# ADC_AD9208.net
KiCad netlist of a schematic drawn in Altium Designer
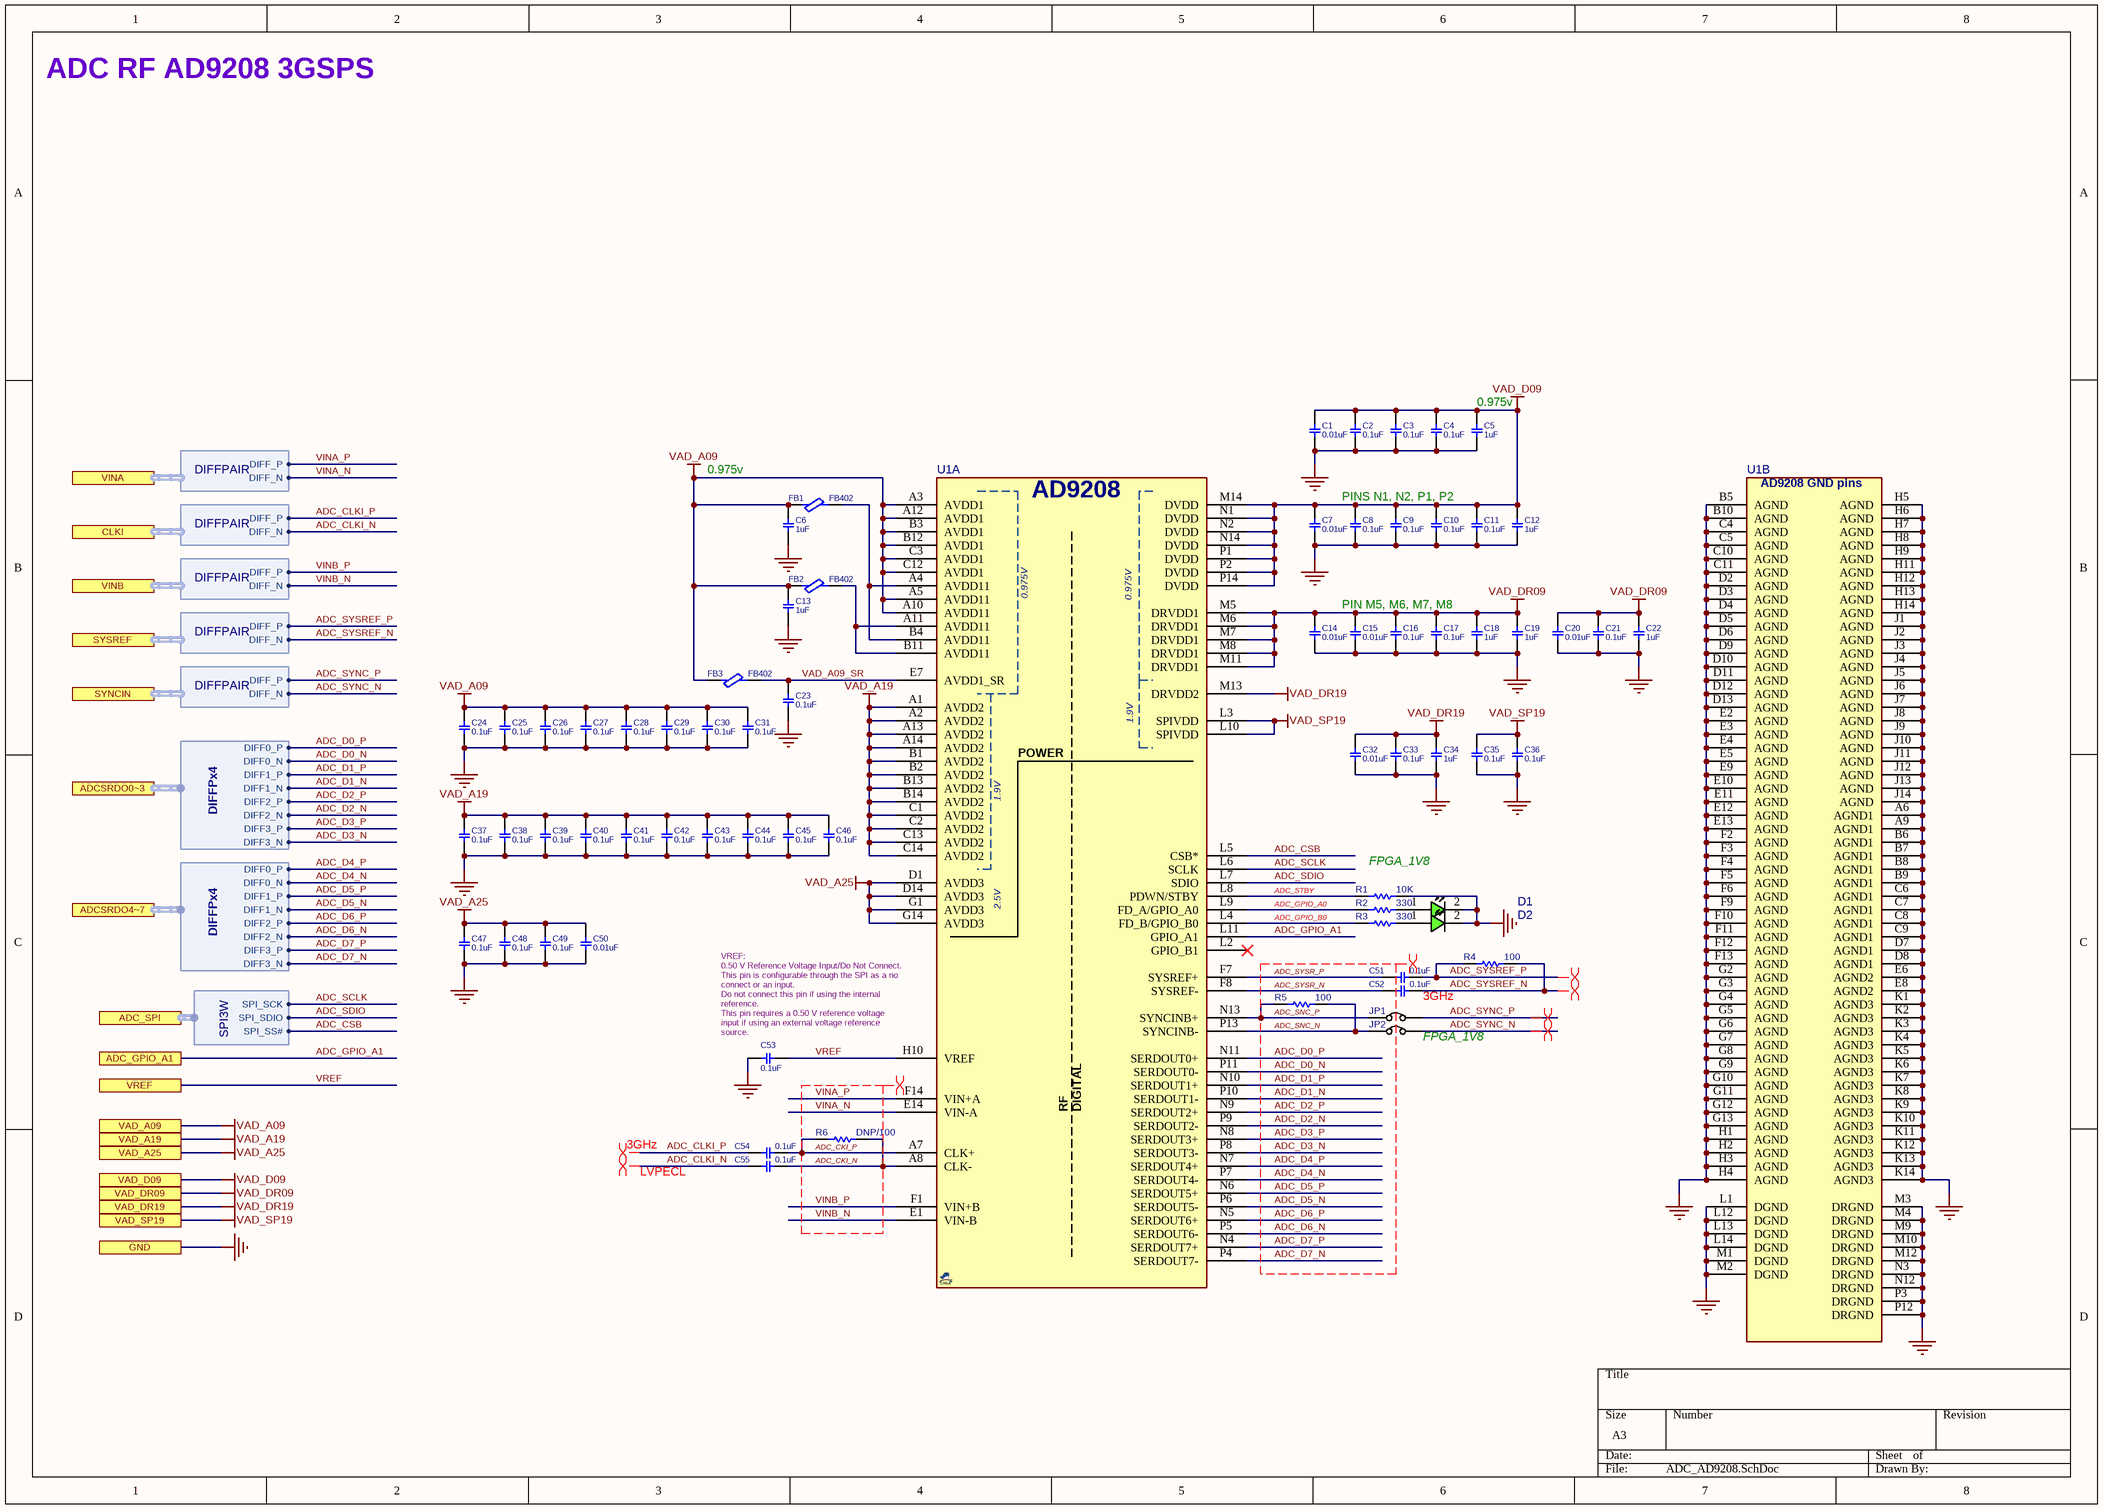
[diagram p0: ADC_AD9208.SchDoc]

(export (version "E")
  (design (tool "Eeschema 10.0.6"))
  (components
    (comp (ref "C1")
      (value "0.01uF")
      (footprint "C0402")
      (description "CAP, MLCC")
      (fields (field (name "MANF_P#") "MANF_PART#") (field (name "MANF") "Murata"))
      (libsource (lib "passive_smd") (part "CAP_SMD_MLCC"))
    )
    (comp (ref "C2")
      (value "0.1uF")
      (footprint "C0402")
      (description "CAP, MLCC")
      (libsource (lib "mlcc_smd_passive") (part "CAP_SMD_MLCC_100n50T"))
    )
    (comp (ref "C3")
      (value "0.1uF")
      (footprint "C0402")
      (description "CAP, MLCC")
      (libsource (lib "mlcc_smd_passive") (part "CAP_SMD_MLCC_100n50T"))
    )
    (comp (ref "C4")
      (value "0.1uF")
      (footprint "C0402")
      (description "CAP, MLCC")
      (libsource (lib "mlcc_smd_passive") (part "CAP_SMD_MLCC_100n50T"))
    )
    (comp (ref "C5")
      (value "1uF")
      (footprint "C0402")
      (description "CAP, MLCC")
      (fields (field (name "MANF_P#") "MANF_PART#") (field (name "MANF") "Murata"))
      (libsource (lib "passive_smd") (part "CAP_SMD_MLCC"))
    )
    (comp (ref "C6")
      (value "1uF")
      (footprint "C0402")
      (description "CAP, MLCC")
      (libsource (lib "mlcc_smd_passive") (part "CAP_SMD_MLCC_100n50T"))
    )
    (comp (ref "C7")
      (value "0.01uF")
      (footprint "C0402")
      (description "CAP, MLCC")
      (fields (field (name "MANF_P#") "MANF_PART#") (field (name "MANF") "Murata"))
      (libsource (lib "passive_smd") (part "CAP_SMD_MLCC"))
    )
    (comp (ref "C8")
      (value "0.1uF")
      (footprint "C0402")
      (description "CAP, MLCC")
      (libsource (lib "mlcc_smd_passive") (part "CAP_SMD_MLCC_100n50T"))
    )
    (comp (ref "C9")
      (value "0.1uF")
      (footprint "C0402")
      (description "CAP, MLCC")
      (libsource (lib "mlcc_smd_passive") (part "CAP_SMD_MLCC_100n50T"))
    )
    (comp (ref "C10")
      (value "0.1uF")
      (footprint "C0402")
      (description "CAP, MLCC")
      (libsource (lib "mlcc_smd_passive") (part "CAP_SMD_MLCC_100n50T"))
    )
    (comp (ref "C11")
      (value "0.1uF")
      (footprint "C0402")
      (description "CAP, MLCC")
      (libsource (lib "mlcc_smd_passive") (part "CAP_SMD_MLCC_100n50T"))
    )
    (comp (ref "C12")
      (value "1uF")
      (footprint "C0402")
      (description "CAP, MLCC")
      (fields (field (name "MANF_P#") "MANF_PART#") (field (name "MANF") "Murata"))
      (libsource (lib "passive_smd") (part "CAP_SMD_MLCC"))
    )
    (comp (ref "C13")
      (value "1uF")
      (footprint "C0402")
      (description "CAP, MLCC")
      (libsource (lib "mlcc_smd_passive") (part "CAP_SMD_MLCC_100n50T"))
    )
    (comp (ref "C14")
      (value "0.01uF")
      (footprint "C0402")
      (description "CAP, MLCC")
      (fields (field (name "MANF_P#") "MANF_PART#") (field (name "MANF") "Murata"))
      (libsource (lib "passive_smd") (part "CAP_SMD_MLCC"))
    )
    (comp (ref "C15")
      (value "0.01uF")
      (footprint "C0402")
      (description "CAP, MLCC")
      (fields (field (name "MANF_P#") "MANF_PART#") (field (name "MANF") "Murata"))
      (libsource (lib "passive_smd") (part "CAP_SMD_MLCC"))
    )
    (comp (ref "C16")
      (value "0.1uF")
      (footprint "C0402")
      (description "CAP, MLCC")
      (libsource (lib "mlcc_smd_passive") (part "CAP_SMD_MLCC_100n50T"))
    )
    (comp (ref "C17")
      (value "0.1uF")
      (footprint "C0402")
      (description "CAP, MLCC")
      (libsource (lib "mlcc_smd_passive") (part "CAP_SMD_MLCC_100n50T"))
    )
    (comp (ref "C18")
      (value "1uF")
      (footprint "C0402")
      (description "CAP, MLCC")
      (fields (field (name "MANF_P#") "MANF_PART#") (field (name "MANF") "Murata"))
      (libsource (lib "passive_smd") (part "CAP_SMD_MLCC"))
    )
    (comp (ref "C19")
      (value "1uF")
      (footprint "C0402")
      (description "CAP, MLCC")
      (fields (field (name "MANF_P#") "MANF_PART#") (field (name "MANF") "Murata"))
      (libsource (lib "passive_smd") (part "CAP_SMD_MLCC"))
    )
    (comp (ref "C20")
      (value "0.01uF")
      (footprint "C0402")
      (description "CAP, MLCC")
      (fields (field (name "MANF_P#") "MANF_PART#") (field (name "MANF") "Murata"))
      (libsource (lib "passive_smd") (part "CAP_SMD_MLCC"))
    )
    (comp (ref "C21")
      (value "0.1uF")
      (footprint "C0402")
      (description "CAP, MLCC")
      (libsource (lib "mlcc_smd_passive") (part "CAP_SMD_MLCC_100n50T"))
    )
    (comp (ref "C22")
      (value "1uF")
      (footprint "C0402")
      (description "CAP, MLCC")
      (fields (field (name "MANF_P#") "MANF_PART#") (field (name "MANF") "Murata"))
      (libsource (lib "passive_smd") (part "CAP_SMD_MLCC"))
    )
    (comp (ref "C23")
      (value "0.1uF")
      (footprint "C0402")
      (description "CAP, MLCC")
      (libsource (lib "mlcc_smd_passive") (part "CAP_SMD_MLCC_100n50T"))
    )
    (comp (ref "C24")
      (value "0.1uF")
      (footprint "C0402")
      (description "CAP, MLCC")
      (libsource (lib "mlcc_smd_passive") (part "CAP_SMD_MLCC_100n50T"))
    )
    (comp (ref "C25")
      (value "0.1uF")
      (footprint "C0402")
      (description "CAP, MLCC")
      (libsource (lib "mlcc_smd_passive") (part "CAP_SMD_MLCC_100n50T"))
    )
    (comp (ref "C26")
      (value "0.1uF")
      (footprint "C0402")
      (description "CAP, MLCC")
      (libsource (lib "mlcc_smd_passive") (part "CAP_SMD_MLCC_100n50T"))
    )
    (comp (ref "C27")
      (value "0.1uF")
      (footprint "C0402")
      (description "CAP, MLCC")
      (libsource (lib "mlcc_smd_passive") (part "CAP_SMD_MLCC_100n50T"))
    )
    (comp (ref "C28")
      (value "0.1uF")
      (footprint "C0402")
      (description "CAP, MLCC")
      (libsource (lib "mlcc_smd_passive") (part "CAP_SMD_MLCC_100n50T"))
    )
    (comp (ref "C29")
      (value "0.1uF")
      (footprint "C0402")
      (description "CAP, MLCC")
      (libsource (lib "mlcc_smd_passive") (part "CAP_SMD_MLCC_100n50T"))
    )
    (comp (ref "C30")
      (value "0.1uF")
      (footprint "C0402")
      (description "CAP, MLCC")
      (libsource (lib "mlcc_smd_passive") (part "CAP_SMD_MLCC_100n50T"))
    )
    (comp (ref "C31")
      (value "0.1uF")
      (footprint "C0402")
      (description "CAP, MLCC")
      (libsource (lib "mlcc_smd_passive") (part "CAP_SMD_MLCC_100n50T"))
    )
    (comp (ref "C32")
      (value "0.01uF")
      (footprint "C0402")
      (description "CAP, MLCC")
      (fields (field (name "MANF_P#") "MANF_PART#") (field (name "MANF") "Murata"))
      (libsource (lib "passive_smd") (part "CAP_SMD_MLCC"))
    )
    (comp (ref "C33")
      (value "0.1uF")
      (footprint "C0402")
      (description "CAP, MLCC")
      (libsource (lib "mlcc_smd_passive") (part "CAP_SMD_MLCC_100n50T"))
    )
    (comp (ref "C34")
      (value "1uF")
      (footprint "C0402")
      (description "CAP, MLCC")
      (fields (field (name "MANF_P#") "MANF_PART#") (field (name "MANF") "Murata"))
      (libsource (lib "passive_smd") (part "CAP_SMD_MLCC"))
    )
    (comp (ref "C35")
      (value "0.1uF")
      (footprint "C0402")
      (description "CAP, MLCC")
      (libsource (lib "mlcc_smd_passive") (part "CAP_SMD_MLCC_100n50T"))
    )
    (comp (ref "C36")
      (value "0.1uF")
      (footprint "C0402")
      (description "CAP, MLCC")
      (libsource (lib "mlcc_smd_passive") (part "CAP_SMD_MLCC_100n50T"))
    )
    (comp (ref "C37")
      (value "0.1uF")
      (footprint "C0402")
      (description "CAP, MLCC")
      (libsource (lib "mlcc_smd_passive") (part "CAP_SMD_MLCC_100n50T"))
    )
    (comp (ref "C38")
      (value "0.1uF")
      (footprint "C0402")
      (description "CAP, MLCC")
      (libsource (lib "mlcc_smd_passive") (part "CAP_SMD_MLCC_100n50T"))
    )
    (comp (ref "C39")
      (value "0.1uF")
      (footprint "C0402")
      (description "CAP, MLCC")
      (libsource (lib "mlcc_smd_passive") (part "CAP_SMD_MLCC_100n50T"))
    )
    (comp (ref "C40")
      (value "0.1uF")
      (footprint "C0402")
      (description "CAP, MLCC")
      (libsource (lib "mlcc_smd_passive") (part "CAP_SMD_MLCC_100n50T"))
    )
    (comp (ref "C41")
      (value "0.1uF")
      (footprint "C0402")
      (description "CAP, MLCC")
      (libsource (lib "mlcc_smd_passive") (part "CAP_SMD_MLCC_100n50T"))
    )
    (comp (ref "C42")
      (value "0.1uF")
      (footprint "C0402")
      (description "CAP, MLCC")
      (libsource (lib "mlcc_smd_passive") (part "CAP_SMD_MLCC_100n50T"))
    )
    (comp (ref "C43")
      (value "0.1uF")
      (footprint "C0402")
      (description "CAP, MLCC")
      (libsource (lib "mlcc_smd_passive") (part "CAP_SMD_MLCC_100n50T"))
    )
    (comp (ref "C44")
      (value "0.1uF")
      (footprint "C0402")
      (description "CAP, MLCC")
      (libsource (lib "mlcc_smd_passive") (part "CAP_SMD_MLCC_100n50T"))
    )
    (comp (ref "C45")
      (value "0.1uF")
      (footprint "C0402")
      (description "CAP, MLCC")
      (libsource (lib "mlcc_smd_passive") (part "CAP_SMD_MLCC_100n50T"))
    )
    (comp (ref "C46")
      (value "0.1uF")
      (footprint "C0402")
      (description "CAP, MLCC")
      (libsource (lib "mlcc_smd_passive") (part "CAP_SMD_MLCC_100n50T"))
    )
    (comp (ref "C47")
      (value "0.1uF")
      (footprint "C0402")
      (description "CAP, MLCC")
      (libsource (lib "mlcc_smd_passive") (part "CAP_SMD_MLCC_100n50T"))
    )
    (comp (ref "C48")
      (value "0.1uF")
      (footprint "C0402")
      (description "CAP, MLCC")
      (libsource (lib "mlcc_smd_passive") (part "CAP_SMD_MLCC_100n50T"))
    )
    (comp (ref "C49")
      (value "0.1uF")
      (footprint "C0402")
      (description "CAP, MLCC")
      (libsource (lib "mlcc_smd_passive") (part "CAP_SMD_MLCC_100n50T"))
    )
    (comp (ref "C50")
      (value "0.01uF")
      (footprint "C0402")
      (description "CAP, MLCC")
      (libsource (lib "mlcc_smd_passive") (part "CAP_SMD_MLCC_100n50T"))
    )
    (comp (ref "C51")
      (value "0.1uF")
      (footprint "C0402")
      (description "CAP, MLCC")
      (libsource (lib "mlcc_smd_passive") (part "CAP_SMD_MLCC_100n50T"))
    )
    (comp (ref "C52")
      (value "0.1uF")
      (footprint "C0402")
      (description "CAP, MLCC")
      (libsource (lib "mlcc_smd_passive") (part "CAP_SMD_MLCC_100n50T"))
    )
    (comp (ref "C53")
      (value "0.1uF")
      (footprint "C0402")
      (description "CAP, MLCC")
      (libsource (lib "mlcc_smd_passive") (part "CAP_SMD_MLCC_100n50T"))
    )
    (comp (ref "C54")
      (value "0.1uF")
      (footprint "C0402")
      (description "CAP, MLCC")
      (libsource (lib "mlcc_smd_passive") (part "CAP_SMD_MLCC_100n50T"))
    )
    (comp (ref "C55")
      (value "0.1uF")
      (footprint "C0402")
      (description "CAP, MLCC")
      (libsource (lib "mlcc_smd_passive") (part "CAP_SMD_MLCC_100n50T"))
    )
    (comp (ref "D1")
      (value "LED603GRN")
      (footprint "LED0603GRN")
      (description "LED, SMD, 0603, GREEN")
      (fields (field (name "MANF") "Kingbright") (field (name "MANF_P#") "APT1608SGC"))
      (libsource (lib "led(diode)") (part "LED_SMD_0603_GRN"))
    )
    (comp (ref "D2")
      (value "LED603GRN")
      (footprint "LED0603GRN")
      (description "LED, SMD, 0603, GREEN")
      (fields (field (name "MANF") "Kingbright") (field (name "MANF_P#") "APT1608SGC"))
      (libsource (lib "led(diode)") (part "LED_SMD_0603_GRN"))
    )
    (comp (ref "FB1")
      (value "FB402")
      (footprint "L0402")
      (description "FERRITE_Bead, 0402, 0.5A, 200mOhm, 120@100MHz")
      (fields (field (name "MANF") "MURATA") (field (name "MANF_P#") "BLM15AG121SN1D"))
      (libsource (lib "emi_filter") (part "FBEAD_SMD_BLM15PD121"))
    )
    (comp (ref "FB2")
      (value "FB402")
      (footprint "L0402")
      (description "FERRITE_Bead, 0402, 0.5A, 200mOhm, 120@100MHz")
      (fields (field (name "MANF") "MURATA") (field (name "MANF_P#") "BLM15AG121SN1D"))
      (libsource (lib "emi_filter") (part "FBEAD_SMD_BLM15PD121"))
    )
    (comp (ref "FB3")
      (value "FB402")
      (footprint "L0402")
      (description "FERRITE_Bead, 0402, 0.5A, 200mOhm, 120@100MHz")
      (fields (field (name "MANF") "MURATA") (field (name "MANF_P#") "BLM15AG121SN1D"))
      (libsource (lib "emi_filter") (part "FBEAD_SMD_BLM15PD121"))
    )
    (comp (ref "JP1")
      (value "JMPSOLDER")
      (footprint "JP_40X50")
      (description "JUMPER,  solder")
      (fields (field (name "MANF") "MANF") (field (name "MANF_P#") "MANF_P#"))
      (libsource (lib "test-tp_jumper") (part "JUMPER_SOLDER"))
    )
    (comp (ref "JP2")
      (value "JMPSOLDER")
      (footprint "JP_40X50")
      (description "JUMPER,  solder")
      (fields (field (name "MANF") "MANF") (field (name "MANF_P#") "MANF_P#"))
      (libsource (lib "test-tp_jumper") (part "JUMPER_SOLDER"))
    )
    (comp (ref "R1")
      (value "10K")
      (footprint "R0402")
      (description "Resistor")
      (libsource (lib "SPassive") (part "Res"))
    )
    (comp (ref "R2")
      (value "330")
      (footprint "R0402")
      (description "Resistor")
      (libsource (lib "SPassive") (part "Res"))
    )
    (comp (ref "R3")
      (value "330")
      (footprint "R0402")
      (description "Resistor")
      (libsource (lib "SPassive") (part "Res"))
    )
    (comp (ref "R4")
      (value "100")
      (footprint "R0402")
      (description "Resistor")
      (libsource (lib "SPassive") (part "Res"))
    )
    (comp (ref "R5")
      (value "100")
      (footprint "R0402")
      (description "Resistor")
      (libsource (lib "SPassive") (part "Res"))
    )
    (comp (ref "R6")
      (value "DNP/100")
      (footprint "R0402")
      (description "Resistor")
      (libsource (lib "SPassive") (part "Res"))
    )
    (comp (ref "U1")
      (value "AD9208")
      (footprint "BGA80_196_S12")
      (description "ADC, 14-Bit, 3Gsps, Dual, JESD204B")
      (fields (field (name "MANF") "Analog Devices") (field (name "MANF_P#") "AD9208BBPZ-3000"))
      (libsource (lib "adc_highspeed") (part "AD9208_BGA196"))
    )
  )
  (nets
    (net (code "4") (name "/ADC_CKI_N") (class "Default")
      (node (ref "C55") (pin "2") (pinfunction "2_2") (pintype "passive"))
      (node (ref "R6") (pin "2") (pinfunction "2_2") (pintype "passive"))
      (node (ref "U1") (pin "A8") (pinfunction "CLK-_A8") (pintype "passive"))
    )
    (net (code "5") (name "/ADC_CKI_P") (class "Default")
      (node (ref "C54") (pin "2") (pinfunction "2_2") (pintype "passive"))
      (node (ref "R6") (pin "1") (pinfunction "1_1") (pintype "passive"))
      (node (ref "U1") (pin "A7") (pinfunction "CLK+_A7") (pintype "passive"))
    )
    (net (code "6") (name "/ADC_CLKI_N") (class "Default")
      (node (ref "C55") (pin "1") (pinfunction "1_1") (pintype "passive"))
    )
    (net (code "7") (name "/ADC_CLKI_P") (class "Default")
      (node (ref "C54") (pin "1") (pinfunction "1_1") (pintype "passive"))
    )
    (net (code "8") (name "/ADC_CSB") (class "Default")
      (node (ref "U1") (pin "L5") (pinfunction "CSB*_L5") (pintype "passive"))
    )
    (net (code "9") (name "/ADC_D0_N") (class "Default")
      (node (ref "U1") (pin "P11") (pinfunction "SERDOUT0-_P11") (pintype "passive"))
    )
    (net (code "10") (name "/ADC_D0_P") (class "Default")
      (node (ref "U1") (pin "N11") (pinfunction "SERDOUT0+_N11") (pintype "passive"))
    )
    (net (code "11") (name "/ADC_D1_N") (class "Default")
      (node (ref "U1") (pin "P10") (pinfunction "SERDOUT1-_P10") (pintype "passive"))
    )
    (net (code "12") (name "/ADC_D1_P") (class "Default")
      (node (ref "U1") (pin "N10") (pinfunction "SERDOUT1+_N10") (pintype "passive"))
    )
    (net (code "13") (name "/ADC_D2_N") (class "Default")
      (node (ref "U1") (pin "P9") (pinfunction "SERDOUT2-_P9") (pintype "passive"))
    )
    (net (code "14") (name "/ADC_D2_P") (class "Default")
      (node (ref "U1") (pin "N9") (pinfunction "SERDOUT2+_N9") (pintype "passive"))
    )
    (net (code "15") (name "/ADC_D3_N") (class "Default")
      (node (ref "U1") (pin "P8") (pinfunction "SERDOUT3-_P8") (pintype "passive"))
    )
    (net (code "16") (name "/ADC_D3_P") (class "Default")
      (node (ref "U1") (pin "N8") (pinfunction "SERDOUT3+_N8") (pintype "passive"))
    )
    (net (code "17") (name "/ADC_D4_N") (class "Default")
      (node (ref "U1") (pin "P7") (pinfunction "SERDOUT4-_P7") (pintype "passive"))
    )
    (net (code "18") (name "/ADC_D4_P") (class "Default")
      (node (ref "U1") (pin "N7") (pinfunction "SERDOUT4+_N7") (pintype "passive"))
    )
    (net (code "19") (name "/ADC_D5_N") (class "Default")
      (node (ref "U1") (pin "P6") (pinfunction "SERDOUT5-_P6") (pintype "passive"))
    )
    (net (code "20") (name "/ADC_D5_P") (class "Default")
      (node (ref "U1") (pin "N6") (pinfunction "SERDOUT5+_N6") (pintype "passive"))
    )
    (net (code "21") (name "/ADC_D6_N") (class "Default")
      (node (ref "U1") (pin "P5") (pinfunction "SERDOUT6-_P5") (pintype "passive"))
    )
    (net (code "22") (name "/ADC_D6_P") (class "Default")
      (node (ref "U1") (pin "N5") (pinfunction "SERDOUT6+_N5") (pintype "passive"))
    )
    (net (code "23") (name "/ADC_D7_N") (class "Default")
      (node (ref "U1") (pin "P4") (pinfunction "SERDOUT7-_P4") (pintype "passive"))
    )
    (net (code "24") (name "/ADC_D7_P") (class "Default")
      (node (ref "U1") (pin "N4") (pinfunction "SERDOUT7+_N4") (pintype "passive"))
    )
    (net (code "25") (name "/ADC_GPIO_A0") (class "Default")
      (node (ref "R2") (pin "1") (pinfunction "1_1") (pintype "passive"))
      (node (ref "U1") (pin "L9") (pinfunction "FD_A/GPIO_A0_L9") (pintype "passive"))
    )
    (net (code "26") (name "/ADC_GPIO_A1") (class "Default")
      (node (ref "U1") (pin "L11") (pinfunction "GPIO_A1_L11") (pintype "passive"))
    )
    (net (code "27") (name "/ADC_GPIO_B0") (class "Default")
      (node (ref "R3") (pin "1") (pinfunction "1_1") (pintype "passive"))
      (node (ref "U1") (pin "L4") (pinfunction "FD_B/GPIO_B0_L4") (pintype "passive"))
    )
    (net (code "28") (name "/ADC_SCLK") (class "Default")
      (node (ref "U1") (pin "L6") (pinfunction "SCLK_L6") (pintype "passive"))
    )
    (net (code "29") (name "/ADC_SDIO") (class "Default")
      (node (ref "U1") (pin "L7") (pinfunction "SDIO_L7") (pintype "passive"))
    )
    (net (code "30") (name "/ADC_SNC_N") (class "Default")
      (node (ref "JP2") (pin "1") (pinfunction "1_1") (pintype "passive"))
      (node (ref "R5") (pin "2") (pinfunction "2_2") (pintype "passive"))
      (node (ref "U1") (pin "P13") (pinfunction "SYNCINB-_P13") (pintype "passive"))
    )
    (net (code "31") (name "/ADC_SNC_P") (class "Default")
      (node (ref "JP1") (pin "1") (pinfunction "1_1") (pintype "passive"))
      (node (ref "R5") (pin "1") (pinfunction "1_1") (pintype "passive"))
      (node (ref "U1") (pin "N13") (pinfunction "SYNCINB+_N13") (pintype "passive"))
    )
    (net (code "32") (name "/ADC_STBY") (class "Default")
      (node (ref "R1") (pin "1") (pinfunction "1_1") (pintype "passive"))
      (node (ref "U1") (pin "L8") (pinfunction "PDWN/STBY_L8") (pintype "passive"))
    )
    (net (code "33") (name "/ADC_SYNC_N") (class "Default")
      (node (ref "JP2") (pin "2") (pinfunction "2_2") (pintype "passive"))
    )
    (net (code "34") (name "/ADC_SYNC_P") (class "Default")
      (node (ref "JP1") (pin "2") (pinfunction "2_2") (pintype "passive"))
    )
    (net (code "35") (name "/ADC_SYSREF_N") (class "Default")
      (node (ref "C52") (pin "2") (pinfunction "2_2") (pintype "passive"))
      (node (ref "R4") (pin "2") (pinfunction "2_2") (pintype "passive"))
    )
    (net (code "36") (name "/ADC_SYSREF_P") (class "Default")
      (node (ref "C51") (pin "2") (pinfunction "2_2") (pintype "passive"))
      (node (ref "R4") (pin "1") (pinfunction "1_1") (pintype "passive"))
    )
    (net (code "37") (name "/ADC_SYSR_N") (class "Default")
      (node (ref "C52") (pin "1") (pinfunction "1_1") (pintype "passive"))
      (node (ref "U1") (pin "F8") (pinfunction "SYSREF-_F8") (pintype "passive"))
    )
    (net (code "38") (name "/ADC_SYSR_P") (class "Default")
      (node (ref "C51") (pin "1") (pinfunction "1_1") (pintype "passive"))
      (node (ref "U1") (pin "F7") (pinfunction "SYSREF+_F7") (pintype "passive"))
    )
    (net (code "39") (name "/VAD_A09_SR") (class "Default")
      (node (ref "C23") (pin "1") (pinfunction "1_1") (pintype "passive"))
      (node (ref "FB3") (pin "2") (pinfunction "2_2") (pintype "passive"))
      (node (ref "U1") (pin "E7") (pinfunction "AVDD1_SR_E7") (pintype "passive"))
    )
    (net (code "40") (name "/VINA_N") (class "Default")
      (node (ref "U1") (pin "E14") (pinfunction "VIN-A_E14") (pintype "passive"))
    )
    (net (code "41") (name "/VINA_P") (class "Default")
      (node (ref "U1") (pin "F14") (pinfunction "VIN+A_F14") (pintype "passive"))
    )
    (net (code "42") (name "/VINB_N") (class "Default")
      (node (ref "U1") (pin "E1") (pinfunction "VIN-B_E1") (pintype "passive"))
    )
    (net (code "43") (name "/VINB_P") (class "Default")
      (node (ref "U1") (pin "F1") (pinfunction "VIN+B_F1") (pintype "passive"))
    )
    (net (code "44") (name "/VREF") (class "Default")
      (node (ref "C53") (pin "2") (pinfunction "2_2") (pintype "passive"))
      (node (ref "U1") (pin "H10") (pinfunction "VREF_H10") (pintype "passive"))
    )
    (net (code "48") (name "GND") (class "Default")
      (node (ref "C1") (pin "2") (pinfunction "2_2") (pintype "passive"))
      (node (ref "C10") (pin "2") (pinfunction "2_2") (pintype "passive"))
      (node (ref "C11") (pin "2") (pinfunction "2_2") (pintype "passive"))
      (node (ref "C12") (pin "2") (pinfunction "2_2") (pintype "passive"))
      (node (ref "C13") (pin "2") (pinfunction "2_2") (pintype "passive"))
      (node (ref "C14") (pin "2") (pinfunction "2_2") (pintype "passive"))
      (node (ref "C15") (pin "2") (pinfunction "2_2") (pintype "passive"))
      (node (ref "C16") (pin "2") (pinfunction "2_2") (pintype "passive"))
      (node (ref "C17") (pin "2") (pinfunction "2_2") (pintype "passive"))
      (node (ref "C18") (pin "2") (pinfunction "2_2") (pintype "passive"))
      (node (ref "C19") (pin "2") (pinfunction "2_2") (pintype "passive"))
      (node (ref "C2") (pin "2") (pinfunction "2_2") (pintype "passive"))
      (node (ref "C20") (pin "2") (pinfunction "2_2") (pintype "passive"))
      (node (ref "C21") (pin "2") (pinfunction "2_2") (pintype "passive"))
      (node (ref "C22") (pin "2") (pinfunction "2_2") (pintype "passive"))
      (node (ref "C23") (pin "2") (pinfunction "2_2") (pintype "passive"))
      (node (ref "C24") (pin "2") (pinfunction "2_2") (pintype "passive"))
      (node (ref "C25") (pin "2") (pinfunction "2_2") (pintype "passive"))
      (node (ref "C26") (pin "2") (pinfunction "2_2") (pintype "passive"))
      (node (ref "C27") (pin "2") (pinfunction "2_2") (pintype "passive"))
      (node (ref "C28") (pin "2") (pinfunction "2_2") (pintype "passive"))
      (node (ref "C29") (pin "2") (pinfunction "2_2") (pintype "passive"))
      (node (ref "C3") (pin "2") (pinfunction "2_2") (pintype "passive"))
      (node (ref "C30") (pin "2") (pinfunction "2_2") (pintype "passive"))
      (node (ref "C31") (pin "2") (pinfunction "2_2") (pintype "passive"))
      (node (ref "C32") (pin "2") (pinfunction "2_2") (pintype "passive"))
      (node (ref "C33") (pin "2") (pinfunction "2_2") (pintype "passive"))
      (node (ref "C34") (pin "2") (pinfunction "2_2") (pintype "passive"))
      (node (ref "C35") (pin "2") (pinfunction "2_2") (pintype "passive"))
      (node (ref "C36") (pin "2") (pinfunction "2_2") (pintype "passive"))
      (node (ref "C37") (pin "2") (pinfunction "2_2") (pintype "passive"))
      (node (ref "C38") (pin "2") (pinfunction "2_2") (pintype "passive"))
      (node (ref "C39") (pin "2") (pinfunction "2_2") (pintype "passive"))
      (node (ref "C4") (pin "2") (pinfunction "2_2") (pintype "passive"))
      (node (ref "C40") (pin "2") (pinfunction "2_2") (pintype "passive"))
      (node (ref "C41") (pin "2") (pinfunction "2_2") (pintype "passive"))
      (node (ref "C42") (pin "2") (pinfunction "2_2") (pintype "passive"))
      (node (ref "C43") (pin "2") (pinfunction "2_2") (pintype "passive"))
      (node (ref "C44") (pin "2") (pinfunction "2_2") (pintype "passive"))
      (node (ref "C45") (pin "2") (pinfunction "2_2") (pintype "passive"))
      (node (ref "C46") (pin "2") (pinfunction "2_2") (pintype "passive"))
      (node (ref "C47") (pin "2") (pinfunction "2_2") (pintype "passive"))
      (node (ref "C48") (pin "2") (pinfunction "2_2") (pintype "passive"))
      (node (ref "C49") (pin "2") (pinfunction "2_2") (pintype "passive"))
      (node (ref "C5") (pin "2") (pinfunction "2_2") (pintype "passive"))
      (node (ref "C50") (pin "2") (pinfunction "2_2") (pintype "passive"))
      (node (ref "C53") (pin "1") (pinfunction "1_1") (pintype "passive"))
      (node (ref "C6") (pin "2") (pinfunction "2_2") (pintype "passive"))
      (node (ref "C7") (pin "2") (pinfunction "2_2") (pintype "passive"))
      (node (ref "C8") (pin "2") (pinfunction "2_2") (pintype "passive"))
      (node (ref "C9") (pin "2") (pinfunction "2_2") (pintype "passive"))
      (node (ref "D1") (pin "2") (pinfunction "CATHODE_2") (pintype "passive"))
      (node (ref "D2") (pin "2") (pinfunction "CATHODE_2") (pintype "passive"))
      (node (ref "R1") (pin "2") (pinfunction "2_2") (pintype "passive"))
      (node (ref "U1") (pin "A6") (pinfunction "AGND1_A6") (pintype "passive"))
      (node (ref "U1") (pin "A9") (pinfunction "AGND1_A9") (pintype "passive"))
      (node (ref "U1") (pin "B10") (pinfunction "AGND_B10") (pintype "passive"))
      (node (ref "U1") (pin "B5") (pinfunction "AGND_B5") (pintype "passive"))
      (node (ref "U1") (pin "B6") (pinfunction "AGND1_B6") (pintype "passive"))
      (node (ref "U1") (pin "B7") (pinfunction "AGND1_B7") (pintype "passive"))
      (node (ref "U1") (pin "B8") (pinfunction "AGND1_B8") (pintype "passive"))
      (node (ref "U1") (pin "B9") (pinfunction "AGND1_B9") (pintype "passive"))
      (node (ref "U1") (pin "C10") (pinfunction "AGND_C10") (pintype "passive"))
      (node (ref "U1") (pin "C11") (pinfunction "AGND_C11") (pintype "passive"))
      (node (ref "U1") (pin "C4") (pinfunction "AGND_C4") (pintype "passive"))
      (node (ref "U1") (pin "C5") (pinfunction "AGND_C5") (pintype "passive"))
      (node (ref "U1") (pin "C6") (pinfunction "AGND1_C6") (pintype "passive"))
      (node (ref "U1") (pin "C7") (pinfunction "AGND1_C7") (pintype "passive"))
      (node (ref "U1") (pin "C8") (pinfunction "AGND1_C8") (pintype "passive"))
      (node (ref "U1") (pin "C9") (pinfunction "AGND1_C9") (pintype "passive"))
      (node (ref "U1") (pin "D10") (pinfunction "AGND_D10") (pintype "passive"))
      (node (ref "U1") (pin "D11") (pinfunction "AGND_D11") (pintype "passive"))
      (node (ref "U1") (pin "D12") (pinfunction "AGND_D12") (pintype "passive"))
      (node (ref "U1") (pin "D13") (pinfunction "AGND_D13") (pintype "passive"))
      (node (ref "U1") (pin "D2") (pinfunction "AGND_D2") (pintype "passive"))
      (node (ref "U1") (pin "D3") (pinfunction "AGND_D3") (pintype "passive"))
      (node (ref "U1") (pin "D4") (pinfunction "AGND_D4") (pintype "passive"))
      (node (ref "U1") (pin "D5") (pinfunction "AGND_D5") (pintype "passive"))
      (node (ref "U1") (pin "D6") (pinfunction "AGND_D6") (pintype "passive"))
      (node (ref "U1") (pin "D7") (pinfunction "AGND1_D7") (pintype "passive"))
      (node (ref "U1") (pin "D8") (pinfunction "AGND1_D8") (pintype "passive"))
      (node (ref "U1") (pin "D9") (pinfunction "AGND_D9") (pintype "passive"))
      (node (ref "U1") (pin "E10") (pinfunction "AGND_E10") (pintype "passive"))
      (node (ref "U1") (pin "E11") (pinfunction "AGND_E11") (pintype "passive"))
      (node (ref "U1") (pin "E12") (pinfunction "AGND_E12") (pintype "passive"))
      (node (ref "U1") (pin "E13") (pinfunction "AGND_E13") (pintype "passive"))
      (node (ref "U1") (pin "E2") (pinfunction "AGND_E2") (pintype "passive"))
      (node (ref "U1") (pin "E3") (pinfunction "AGND_E3") (pintype "passive"))
      (node (ref "U1") (pin "E4") (pinfunction "AGND_E4") (pintype "passive"))
      (node (ref "U1") (pin "E5") (pinfunction "AGND_E5") (pintype "passive"))
      (node (ref "U1") (pin "E6") (pinfunction "AGND2_E6") (pintype "passive"))
      (node (ref "U1") (pin "E8") (pinfunction "AGND2_E8") (pintype "passive"))
      (node (ref "U1") (pin "E9") (pinfunction "AGND_E9") (pintype "passive"))
      (node (ref "U1") (pin "F10") (pinfunction "AGND_F10") (pintype "passive"))
      (node (ref "U1") (pin "F11") (pinfunction "AGND_F11") (pintype "passive"))
      (node (ref "U1") (pin "F12") (pinfunction "AGND_F12") (pintype "passive"))
      (node (ref "U1") (pin "F13") (pinfunction "AGND_F13") (pintype "passive"))
      (node (ref "U1") (pin "F2") (pinfunction "AGND_F2") (pintype "passive"))
      (node (ref "U1") (pin "F3") (pinfunction "AGND_F3") (pintype "passive"))
      (node (ref "U1") (pin "F4") (pinfunction "AGND_F4") (pintype "passive"))
      (node (ref "U1") (pin "F5") (pinfunction "AGND_F5") (pintype "passive"))
      (node (ref "U1") (pin "F6") (pinfunction "AGND_F6") (pintype "passive"))
      (node (ref "U1") (pin "F9") (pinfunction "AGND_F9") (pintype "passive"))
      (node (ref "U1") (pin "G10") (pinfunction "AGND_G10") (pintype "passive"))
      (node (ref "U1") (pin "G11") (pinfunction "AGND_G11") (pintype "passive"))
      (node (ref "U1") (pin "G12") (pinfunction "AGND_G12") (pintype "passive"))
      (node (ref "U1") (pin "G13") (pinfunction "AGND_G13") (pintype "passive"))
      (node (ref "U1") (pin "G2") (pinfunction "AGND_G2") (pintype "passive"))
      (node (ref "U1") (pin "G3") (pinfunction "AGND_G3") (pintype "passive"))
      (node (ref "U1") (pin "G4") (pinfunction "AGND_G4") (pintype "passive"))
      (node (ref "U1") (pin "G5") (pinfunction "AGND_G5") (pintype "passive"))
      (node (ref "U1") (pin "G6") (pinfunction "AGND_G6") (pintype "passive"))
      (node (ref "U1") (pin "G7") (pinfunction "AGND_G7") (pintype "passive"))
      (node (ref "U1") (pin "G8") (pinfunction "AGND_G8") (pintype "passive"))
      (node (ref "U1") (pin "G9") (pinfunction "AGND_G9") (pintype "passive"))
      (node (ref "U1") (pin "H1") (pinfunction "AGND_H1") (pintype "passive"))
      (node (ref "U1") (pin "H11") (pinfunction "AGND_H11") (pintype "passive"))
      (node (ref "U1") (pin "H12") (pinfunction "AGND_H12") (pintype "passive"))
      (node (ref "U1") (pin "H13") (pinfunction "AGND_H13") (pintype "passive"))
      (node (ref "U1") (pin "H14") (pinfunction "AGND_H14") (pintype "passive"))
      (node (ref "U1") (pin "H2") (pinfunction "AGND_H2") (pintype "passive"))
      (node (ref "U1") (pin "H3") (pinfunction "AGND_H3") (pintype "passive"))
      (node (ref "U1") (pin "H4") (pinfunction "AGND_H4") (pintype "passive"))
      (node (ref "U1") (pin "H5") (pinfunction "AGND_H5") (pintype "passive"))
      (node (ref "U1") (pin "H6") (pinfunction "AGND_H6") (pintype "passive"))
      (node (ref "U1") (pin "H7") (pinfunction "AGND_H7") (pintype "passive"))
      (node (ref "U1") (pin "H8") (pinfunction "AGND_H8") (pintype "passive"))
      (node (ref "U1") (pin "H9") (pinfunction "AGND_H9") (pintype "passive"))
      (node (ref "U1") (pin "J1") (pinfunction "AGND_J1") (pintype "passive"))
      (node (ref "U1") (pin "J10") (pinfunction "AGND_J10") (pintype "passive"))
      (node (ref "U1") (pin "J11") (pinfunction "AGND_J11") (pintype "passive"))
      (node (ref "U1") (pin "J12") (pinfunction "AGND_J12") (pintype "passive"))
      (node (ref "U1") (pin "J13") (pinfunction "AGND_J13") (pintype "passive"))
      (node (ref "U1") (pin "J14") (pinfunction "AGND_J14") (pintype "passive"))
      (node (ref "U1") (pin "J2") (pinfunction "AGND_J2") (pintype "passive"))
      (node (ref "U1") (pin "J3") (pinfunction "AGND_J3") (pintype "passive"))
      (node (ref "U1") (pin "J4") (pinfunction "AGND_J4") (pintype "passive"))
      (node (ref "U1") (pin "J5") (pinfunction "AGND_J5") (pintype "passive"))
      (node (ref "U1") (pin "J6") (pinfunction "AGND_J6") (pintype "passive"))
      (node (ref "U1") (pin "J7") (pinfunction "AGND_J7") (pintype "passive"))
      (node (ref "U1") (pin "J8") (pinfunction "AGND_J8") (pintype "passive"))
      (node (ref "U1") (pin "J9") (pinfunction "AGND_J9") (pintype "passive"))
      (node (ref "U1") (pin "K1") (pinfunction "AGND3_K1") (pintype "passive"))
      (node (ref "U1") (pin "K10") (pinfunction "AGND3_K10") (pintype "passive"))
      (node (ref "U1") (pin "K11") (pinfunction "AGND3_K11") (pintype "passive"))
      (node (ref "U1") (pin "K12") (pinfunction "AGND3_K12") (pintype "passive"))
      (node (ref "U1") (pin "K13") (pinfunction "AGND3_K13") (pintype "passive"))
      (node (ref "U1") (pin "K14") (pinfunction "AGND3_K14") (pintype "passive"))
      (node (ref "U1") (pin "K2") (pinfunction "AGND3_K2") (pintype "passive"))
      (node (ref "U1") (pin "K3") (pinfunction "AGND3_K3") (pintype "passive"))
      (node (ref "U1") (pin "K4") (pinfunction "AGND3_K4") (pintype "passive"))
      (node (ref "U1") (pin "K5") (pinfunction "AGND3_K5") (pintype "passive"))
      (node (ref "U1") (pin "K6") (pinfunction "AGND3_K6") (pintype "passive"))
      (node (ref "U1") (pin "K7") (pinfunction "AGND3_K7") (pintype "passive"))
      (node (ref "U1") (pin "K8") (pinfunction "AGND3_K8") (pintype "passive"))
      (node (ref "U1") (pin "K9") (pinfunction "AGND3_K9") (pintype "passive"))
      (node (ref "U1") (pin "L1") (pinfunction "DGND_L1") (pintype "passive"))
      (node (ref "U1") (pin "L12") (pinfunction "DGND_L12") (pintype "passive"))
      (node (ref "U1") (pin "L13") (pinfunction "DGND_L13") (pintype "passive"))
      (node (ref "U1") (pin "L14") (pinfunction "DGND_L14") (pintype "passive"))
      (node (ref "U1") (pin "M1") (pinfunction "DGND_M1") (pintype "passive"))
      (node (ref "U1") (pin "M10") (pinfunction "DRGND_M10") (pintype "passive"))
      (node (ref "U1") (pin "M12") (pinfunction "DRGND_M12") (pintype "passive"))
      (node (ref "U1") (pin "M2") (pinfunction "DGND_M2") (pintype "passive"))
      (node (ref "U1") (pin "M3") (pinfunction "DRGND_M3") (pintype "passive"))
      (node (ref "U1") (pin "M4") (pinfunction "DRGND_M4") (pintype "passive"))
      (node (ref "U1") (pin "M9") (pinfunction "DRGND_M9") (pintype "passive"))
      (node (ref "U1") (pin "N12") (pinfunction "DRGND_N12") (pintype "passive"))
      (node (ref "U1") (pin "N3") (pinfunction "DRGND_N3") (pintype "passive"))
      (node (ref "U1") (pin "P12") (pinfunction "DRGND_P12") (pintype "passive"))
      (node (ref "U1") (pin "P3") (pinfunction "DRGND_P3") (pintype "passive"))
    )
    (net (code "49") (name "Net-(D1-ANODE)") (class "Default")
      (node (ref "D1") (pin "1") (pinfunction "ANODE_1") (pintype "passive"))
      (node (ref "R2") (pin "2") (pinfunction "2_2") (pintype "passive"))
    )
    (net (code "50") (name "Net-(D2-ANODE)") (class "Default")
      (node (ref "D2") (pin "1") (pinfunction "ANODE_1") (pintype "passive"))
      (node (ref "R3") (pin "2") (pinfunction "2_2") (pintype "passive"))
    )
    (net (code "51") (name "Net-(FB1-Pad2)") (class "Default")
      (node (ref "FB1") (pin "2") (pinfunction "2_2") (pintype "passive"))
      (node (ref "U1") (pin "A4") (pinfunction "AVDD11_A4") (pintype "passive"))
      (node (ref "U1") (pin "B4") (pinfunction "AVDD11_B4") (pintype "passive"))
    )
    (net (code "52") (name "Net-(FB2-Pad2)") (class "Default")
      (node (ref "FB2") (pin "2") (pinfunction "2_2") (pintype "passive"))
      (node (ref "U1") (pin "A11") (pinfunction "AVDD11_A11") (pintype "passive"))
      (node (ref "U1") (pin "B11") (pinfunction "AVDD11_B11") (pintype "passive"))
    )
    (net (code "53") (name "VAD_A09") (class "Default")
      (node (ref "C13") (pin "1") (pinfunction "1_1") (pintype "passive"))
      (node (ref "C24") (pin "1") (pinfunction "1_1") (pintype "passive"))
      (node (ref "C25") (pin "1") (pinfunction "1_1") (pintype "passive"))
      (node (ref "C26") (pin "1") (pinfunction "1_1") (pintype "passive"))
      (node (ref "C27") (pin "1") (pinfunction "1_1") (pintype "passive"))
      (node (ref "C28") (pin "1") (pinfunction "1_1") (pintype "passive"))
      (node (ref "C29") (pin "1") (pinfunction "1_1") (pintype "passive"))
      (node (ref "C30") (pin "1") (pinfunction "1_1") (pintype "passive"))
      (node (ref "C31") (pin "1") (pinfunction "1_1") (pintype "passive"))
      (node (ref "C6") (pin "1") (pinfunction "1_1") (pintype "passive"))
      (node (ref "FB1") (pin "1") (pinfunction "1_1") (pintype "passive"))
      (node (ref "FB2") (pin "1") (pinfunction "1_1") (pintype "passive"))
      (node (ref "FB3") (pin "1") (pinfunction "1_1") (pintype "passive"))
      (node (ref "U1") (pin "A10") (pinfunction "AVDD11_A10") (pintype "passive"))
      (node (ref "U1") (pin "A12") (pinfunction "AVDD1_A12") (pintype "passive"))
      (node (ref "U1") (pin "A3") (pinfunction "AVDD1_A3") (pintype "passive"))
      (node (ref "U1") (pin "A5") (pinfunction "AVDD11_A5") (pintype "passive"))
      (node (ref "U1") (pin "B12") (pinfunction "AVDD1_B12") (pintype "passive"))
      (node (ref "U1") (pin "B3") (pinfunction "AVDD1_B3") (pintype "passive"))
      (node (ref "U1") (pin "C12") (pinfunction "AVDD1_C12") (pintype "passive"))
      (node (ref "U1") (pin "C3") (pinfunction "AVDD1_C3") (pintype "passive"))
    )
    (net (code "54") (name "VAD_A19") (class "Default")
      (node (ref "C37") (pin "1") (pinfunction "1_1") (pintype "passive"))
      (node (ref "C38") (pin "1") (pinfunction "1_1") (pintype "passive"))
      (node (ref "C39") (pin "1") (pinfunction "1_1") (pintype "passive"))
      (node (ref "C40") (pin "1") (pinfunction "1_1") (pintype "passive"))
      (node (ref "C41") (pin "1") (pinfunction "1_1") (pintype "passive"))
      (node (ref "C42") (pin "1") (pinfunction "1_1") (pintype "passive"))
      (node (ref "C43") (pin "1") (pinfunction "1_1") (pintype "passive"))
      (node (ref "C44") (pin "1") (pinfunction "1_1") (pintype "passive"))
      (node (ref "C45") (pin "1") (pinfunction "1_1") (pintype "passive"))
      (node (ref "C46") (pin "1") (pinfunction "1_1") (pintype "passive"))
      (node (ref "U1") (pin "A1") (pinfunction "AVDD2_A1") (pintype "passive"))
      (node (ref "U1") (pin "A13") (pinfunction "AVDD2_A13") (pintype "passive"))
      (node (ref "U1") (pin "A14") (pinfunction "AVDD2_A14") (pintype "passive"))
      (node (ref "U1") (pin "A2") (pinfunction "AVDD2_A2") (pintype "passive"))
      (node (ref "U1") (pin "B1") (pinfunction "AVDD2_B1") (pintype "passive"))
      (node (ref "U1") (pin "B13") (pinfunction "AVDD2_B13") (pintype "passive"))
      (node (ref "U1") (pin "B14") (pinfunction "AVDD2_B14") (pintype "passive"))
      (node (ref "U1") (pin "B2") (pinfunction "AVDD2_B2") (pintype "passive"))
      (node (ref "U1") (pin "C1") (pinfunction "AVDD2_C1") (pintype "passive"))
      (node (ref "U1") (pin "C13") (pinfunction "AVDD2_C13") (pintype "passive"))
      (node (ref "U1") (pin "C14") (pinfunction "AVDD2_C14") (pintype "passive"))
      (node (ref "U1") (pin "C2") (pinfunction "AVDD2_C2") (pintype "passive"))
    )
    (net (code "55") (name "VAD_A25") (class "Default")
      (node (ref "C47") (pin "1") (pinfunction "1_1") (pintype "passive"))
      (node (ref "C48") (pin "1") (pinfunction "1_1") (pintype "passive"))
      (node (ref "C49") (pin "1") (pinfunction "1_1") (pintype "passive"))
      (node (ref "C50") (pin "1") (pinfunction "1_1") (pintype "passive"))
      (node (ref "U1") (pin "D1") (pinfunction "AVDD3_D1") (pintype "passive"))
      (node (ref "U1") (pin "D14") (pinfunction "AVDD3_D14") (pintype "passive"))
      (node (ref "U1") (pin "G1") (pinfunction "AVDD3_G1") (pintype "passive"))
      (node (ref "U1") (pin "G14") (pinfunction "AVDD3_G14") (pintype "passive"))
    )
    (net (code "56") (name "VAD_D09") (class "Default")
      (node (ref "C1") (pin "1") (pinfunction "1_1") (pintype "passive"))
      (node (ref "C10") (pin "1") (pinfunction "1_1") (pintype "passive"))
      (node (ref "C11") (pin "1") (pinfunction "1_1") (pintype "passive"))
      (node (ref "C12") (pin "1") (pinfunction "1_1") (pintype "passive"))
      (node (ref "C2") (pin "1") (pinfunction "1_1") (pintype "passive"))
      (node (ref "C3") (pin "1") (pinfunction "1_1") (pintype "passive"))
      (node (ref "C4") (pin "1") (pinfunction "1_1") (pintype "passive"))
      (node (ref "C5") (pin "1") (pinfunction "1_1") (pintype "passive"))
      (node (ref "C7") (pin "1") (pinfunction "1_1") (pintype "passive"))
      (node (ref "C8") (pin "1") (pinfunction "1_1") (pintype "passive"))
      (node (ref "C9") (pin "1") (pinfunction "1_1") (pintype "passive"))
      (node (ref "U1") (pin "M14") (pinfunction "DVDD_M14") (pintype "passive"))
      (node (ref "U1") (pin "N1") (pinfunction "DVDD_N1") (pintype "passive"))
      (node (ref "U1") (pin "N14") (pinfunction "DVDD_N14") (pintype "passive"))
      (node (ref "U1") (pin "N2") (pinfunction "DVDD_N2") (pintype "passive"))
      (node (ref "U1") (pin "P1") (pinfunction "DVDD_P1") (pintype "passive"))
      (node (ref "U1") (pin "P14") (pinfunction "DVDD_P14") (pintype "passive"))
      (node (ref "U1") (pin "P2") (pinfunction "DVDD_P2") (pintype "passive"))
    )
    (net (code "57") (name "VAD_DR09") (class "Default")
      (node (ref "C14") (pin "1") (pinfunction "1_1") (pintype "passive"))
      (node (ref "C15") (pin "1") (pinfunction "1_1") (pintype "passive"))
      (node (ref "C16") (pin "1") (pinfunction "1_1") (pintype "passive"))
      (node (ref "C17") (pin "1") (pinfunction "1_1") (pintype "passive"))
      (node (ref "C18") (pin "1") (pinfunction "1_1") (pintype "passive"))
      (node (ref "C19") (pin "1") (pinfunction "1_1") (pintype "passive"))
      (node (ref "C20") (pin "1") (pinfunction "1_1") (pintype "passive"))
      (node (ref "C21") (pin "1") (pinfunction "1_1") (pintype "passive"))
      (node (ref "C22") (pin "1") (pinfunction "1_1") (pintype "passive"))
      (node (ref "U1") (pin "M11") (pinfunction "DRVDD1_M11") (pintype "passive"))
      (node (ref "U1") (pin "M5") (pinfunction "DRVDD1_M5") (pintype "passive"))
      (node (ref "U1") (pin "M6") (pinfunction "DRVDD1_M6") (pintype "passive"))
      (node (ref "U1") (pin "M7") (pinfunction "DRVDD1_M7") (pintype "passive"))
      (node (ref "U1") (pin "M8") (pinfunction "DRVDD1_M8") (pintype "passive"))
    )
    (net (code "58") (name "VAD_DR19") (class "Default")
      (node (ref "C32") (pin "1") (pinfunction "1_1") (pintype "passive"))
      (node (ref "C33") (pin "1") (pinfunction "1_1") (pintype "passive"))
      (node (ref "C34") (pin "1") (pinfunction "1_1") (pintype "passive"))
      (node (ref "U1") (pin "M13") (pinfunction "DRVDD2_M13") (pintype "passive"))
    )
    (net (code "59") (name "VAD_SP19") (class "Default")
      (node (ref "C35") (pin "1") (pinfunction "1_1") (pintype "passive"))
      (node (ref "C36") (pin "1") (pinfunction "1_1") (pintype "passive"))
      (node (ref "U1") (pin "L10") (pinfunction "SPIVDD_L10") (pintype "passive"))
      (node (ref "U1") (pin "L3") (pinfunction "SPIVDD_L3") (pintype "passive"))
    )
    (net (code "60") (name "unconnected-(U1A-GPIO_B1-PadL2)") (class "Default")
      (node (ref "U1") (pin "L2") (pinfunction "GPIO_B1_L2") (pintype "passive+no_connect"))
    )
  )
)
